# ETH_PHY_SFP.net
KiCad netlist of a schematic drawn in Altium Designer
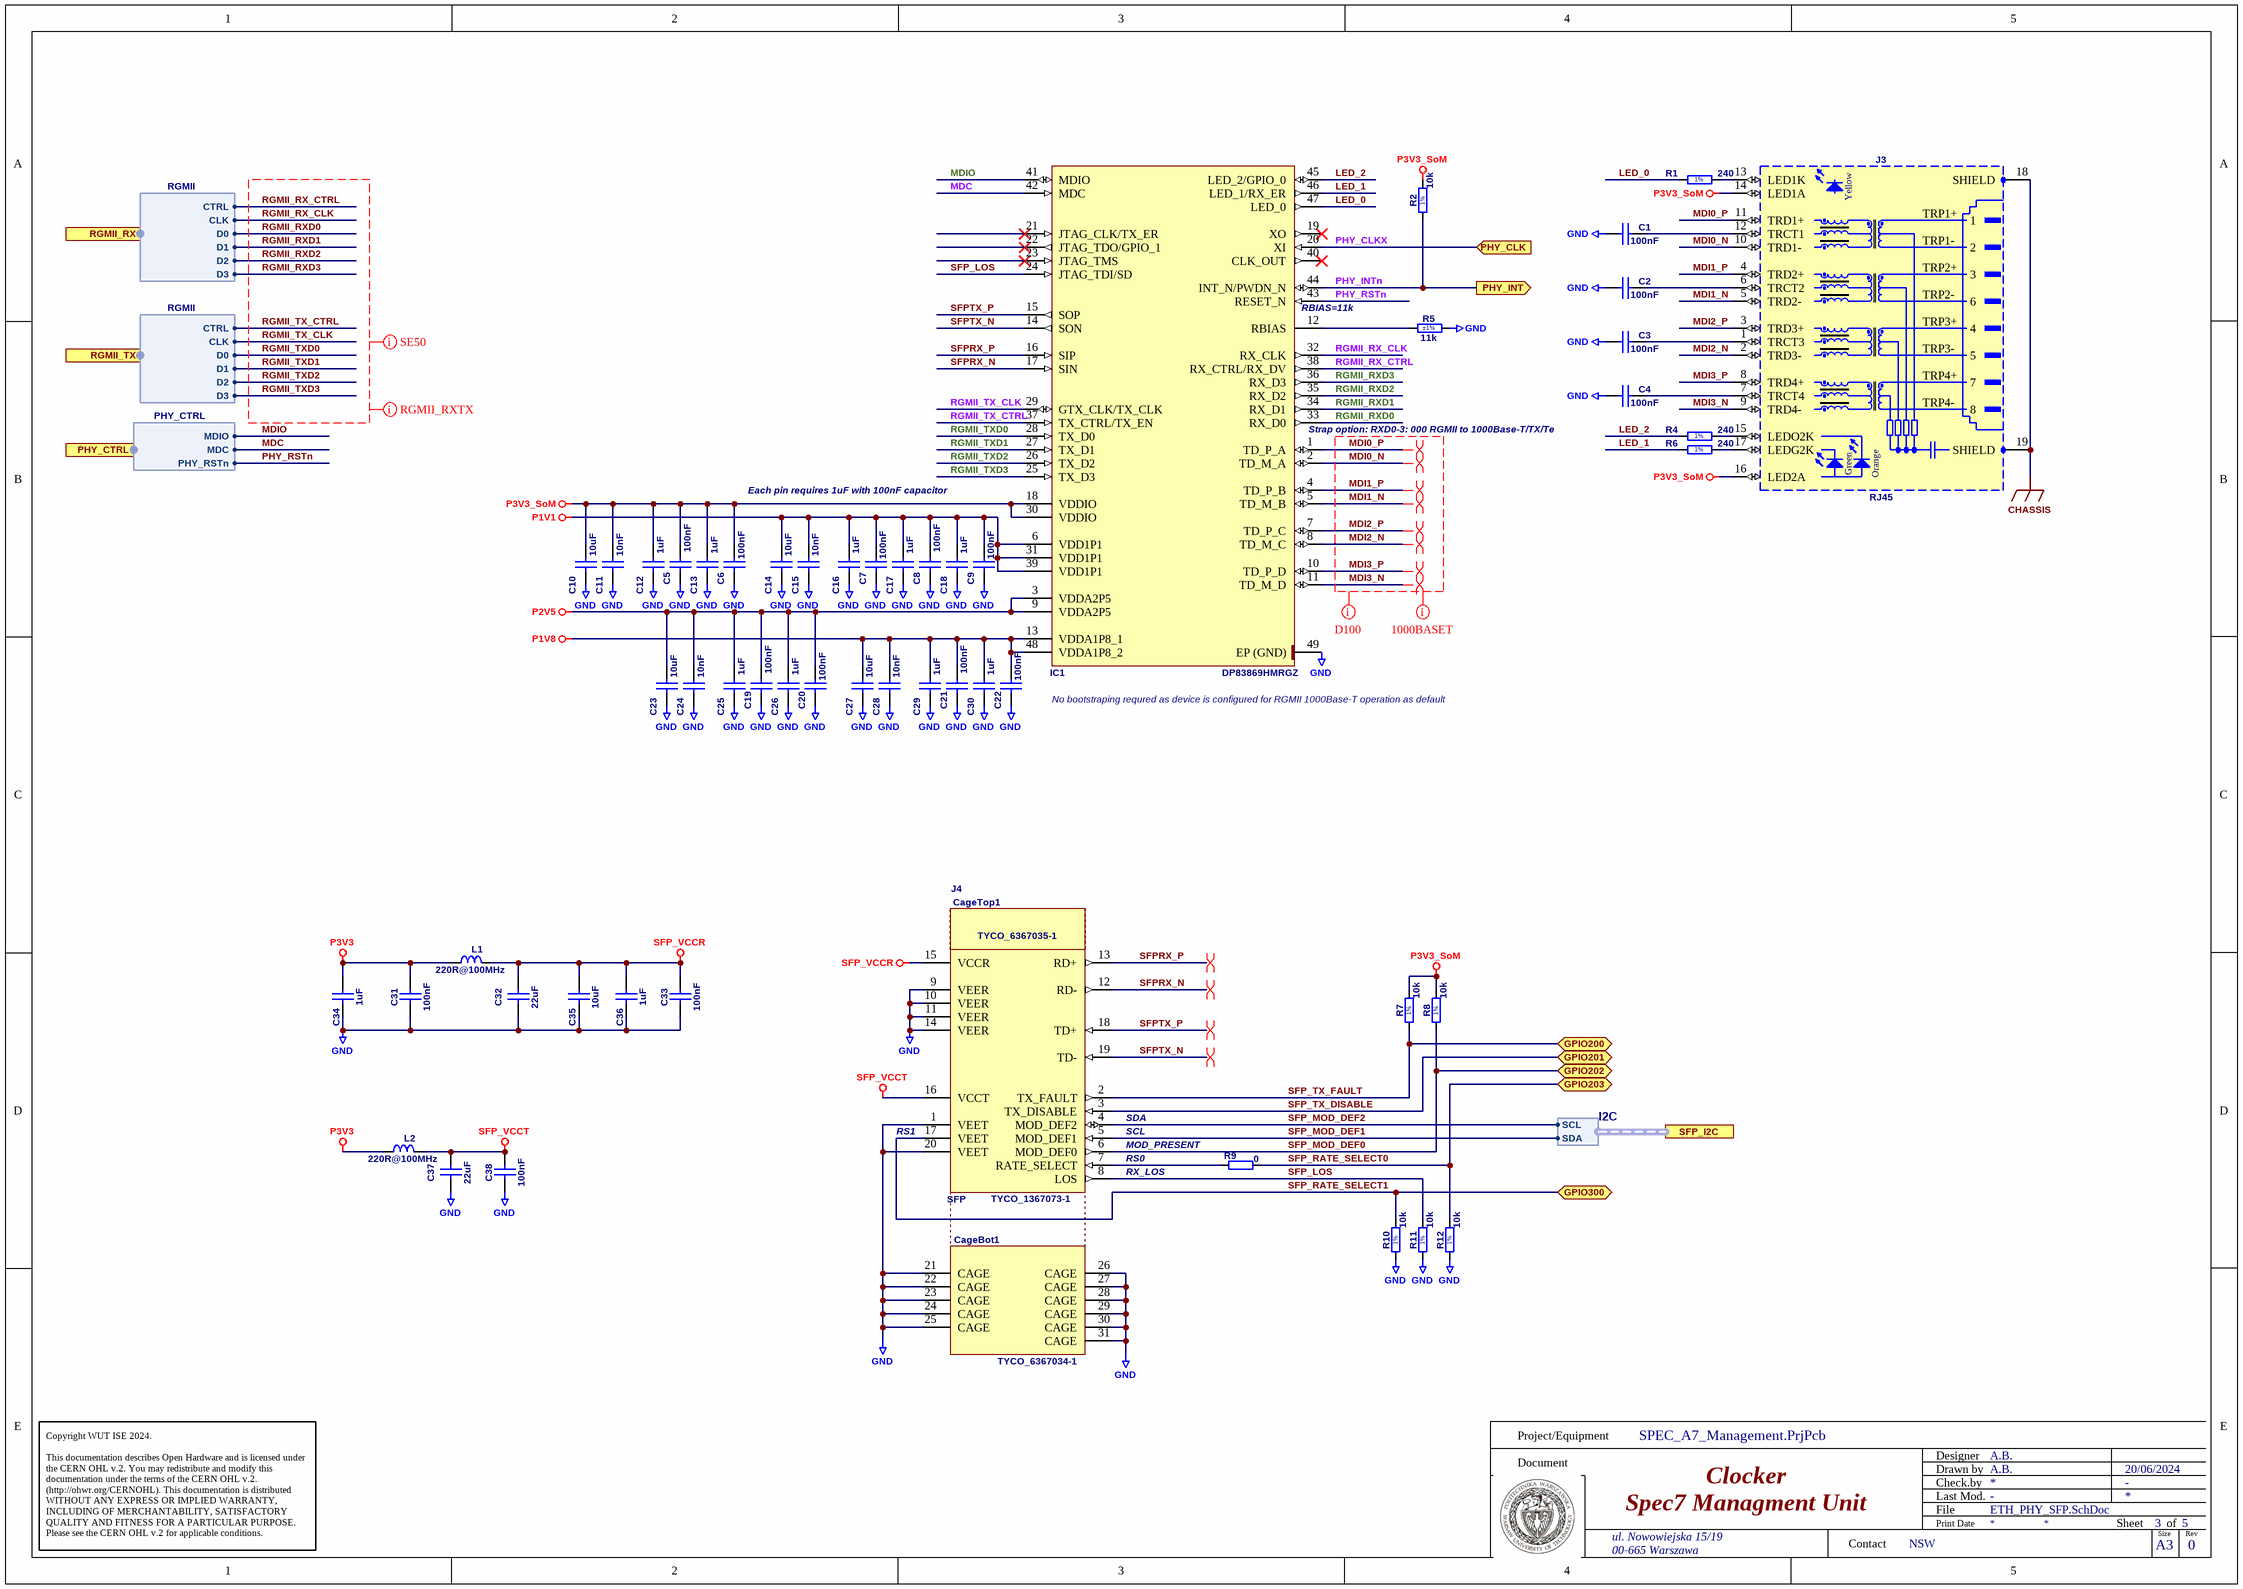
[diagram p0: ETH_PHY_SFP.SchDoc]

(export (version "E")
  (design (tool "Eeschema 10.0.6"))
  (components
    (comp (ref "C1")
      (value "100nF")
      (footprint "CAPC1005X55N")
      (description "Non-polarised capacitor")
      (fields
        (field (name "PART NUMBER") "CC0402_100NF_16V_10%_X7R")
        (field (name "VOLTAGE") "16V")
        (field (name "AUTHOR") "CERN DEM JLC")
      )
      (libsource (lib "Capacitors") (part "Capacitor - non polarized"))
    )
    (comp (ref "C2")
      (value "100nF")
      (footprint "CAPC1005X55N")
      (description "Non-polarised capacitor")
      (fields
        (field (name "PART NUMBER") "CC0402_100NF_16V_10%_X7R")
        (field (name "VOLTAGE") "16V")
        (field (name "AUTHOR") "CERN DEM JLC")
      )
      (libsource (lib "Capacitors") (part "Capacitor - non polarized"))
    )
    (comp (ref "C3")
      (value "100nF")
      (footprint "CAPC1005X55N")
      (description "Non-polarised capacitor")
      (fields
        (field (name "PART NUMBER") "CC0402_100NF_16V_10%_X7R")
        (field (name "VOLTAGE") "16V")
        (field (name "AUTHOR") "CERN DEM JLC")
      )
      (libsource (lib "Capacitors") (part "Capacitor - non polarized"))
    )
    (comp (ref "C4")
      (value "100nF")
      (footprint "CAPC1005X55N")
      (description "Non-polarised capacitor")
      (fields
        (field (name "PART NUMBER") "CC0402_100NF_16V_10%_X7R")
        (field (name "VOLTAGE") "16V")
        (field (name "AUTHOR") "CERN DEM JLC")
      )
      (libsource (lib "Capacitors") (part "Capacitor - non polarized"))
    )
    (comp (ref "C5")
      (value "100nF")
      (footprint "CAPC1005X55N")
      (description "Non-polarised capacitor")
      (fields
        (field (name "PART NUMBER") "CC0402_100NF_16V_10%_X7R")
        (field (name "VOLTAGE") "16V")
        (field (name "AUTHOR") "CERN DEM JLC")
      )
      (libsource (lib "Capacitors") (part "Capacitor - non polarized"))
    )
    (comp (ref "C6")
      (value "100nF")
      (footprint "CAPC1005X55N")
      (description "Non-polarised capacitor")
      (fields
        (field (name "PART NUMBER") "CC0402_100NF_16V_10%_X7R")
        (field (name "VOLTAGE") "16V")
        (field (name "AUTHOR") "CERN DEM JLC")
      )
      (libsource (lib "Capacitors") (part "Capacitor - non polarized"))
    )
    (comp (ref "C7")
      (value "100nF")
      (footprint "CAPC1005X55N")
      (description "Non-polarised capacitor")
      (fields
        (field (name "PART NUMBER") "CC0402_100NF_16V_10%_X7R")
        (field (name "VOLTAGE") "16V")
        (field (name "AUTHOR") "CERN DEM JLC")
      )
      (libsource (lib "Capacitors") (part "Capacitor - non polarized"))
    )
    (comp (ref "C8")
      (value "100nF")
      (footprint "CAPC1005X55N")
      (description "Non-polarised capacitor")
      (fields
        (field (name "PART NUMBER") "CC0402_100NF_16V_10%_X7R")
        (field (name "VOLTAGE") "16V")
        (field (name "AUTHOR") "CERN DEM JLC")
      )
      (libsource (lib "Capacitors") (part "Capacitor - non polarized"))
    )
    (comp (ref "C9")
      (value "100nF")
      (footprint "CAPC1005X55N")
      (description "Non-polarised capacitor")
      (fields
        (field (name "PART NUMBER") "CC0402_100NF_16V_10%_X7R")
        (field (name "VOLTAGE") "16V")
        (field (name "AUTHOR") "CERN DEM JLC")
      )
      (libsource (lib "Capacitors") (part "Capacitor - non polarized"))
    )
    (comp (ref "C10")
      (value "10uF")
      (footprint "CAPC1608X80N")
      (description "Non-polarised capacitor")
      (fields
        (field (name "PART NUMBER") "CC0603_10UF_16V_20%_X5R")
        (field (name "VOLTAGE") "16V")
        (field (name "AUTHOR") "CERN DEM MR")
      )
      (libsource (lib "Capacitors") (part "Capacitor - non polarized"))
    )
    (comp (ref "C11")
      (value "10nF")
      (footprint "CAPC1005X55N")
      (description "Non-polarised capacitor")
      (fields
        (field (name "PART NUMBER") "CC0402_10NF_16V_10%_X7R")
        (field (name "VOLTAGE") "16V")
        (field (name "AUTHOR") "CERN DEM JLC")
      )
      (libsource (lib "Capacitors") (part "Capacitor - non polarized"))
    )
    (comp (ref "C12")
      (value "1uF")
      (footprint "CAPC1005X55N")
      (description "Non-polarised capacitor")
      (fields
        (field (name "PART NUMBER") "CC0402_1UF_16V_10%_X5R")
        (field (name "VOLTAGE") "16V")
        (field (name "AUTHOR") "CERN DEM JLC")
      )
      (libsource (lib "Capacitors") (part "Capacitor - non polarized"))
    )
    (comp (ref "C13")
      (value "1uF")
      (footprint "CAPC1005X55N")
      (description "Non-polarised capacitor")
      (fields
        (field (name "PART NUMBER") "CC0402_1UF_16V_10%_X5R")
        (field (name "VOLTAGE") "16V")
        (field (name "AUTHOR") "CERN DEM JLC")
      )
      (libsource (lib "Capacitors") (part "Capacitor - non polarized"))
    )
    (comp (ref "C14")
      (value "10uF")
      (footprint "CAPC1608X80N")
      (description "Non-polarised capacitor")
      (fields
        (field (name "PART NUMBER") "CC0603_10UF_16V_20%_X5R")
        (field (name "VOLTAGE") "16V")
        (field (name "AUTHOR") "CERN DEM MR")
      )
      (libsource (lib "Capacitors") (part "Capacitor - non polarized"))
    )
    (comp (ref "C15")
      (value "10nF")
      (footprint "CAPC1005X55N")
      (description "Non-polarised capacitor")
      (fields
        (field (name "PART NUMBER") "CC0402_10NF_16V_10%_X7R")
        (field (name "VOLTAGE") "16V")
        (field (name "AUTHOR") "CERN DEM JLC")
      )
      (libsource (lib "Capacitors") (part "Capacitor - non polarized"))
    )
    (comp (ref "C16")
      (value "1uF")
      (footprint "CAPC1005X55N")
      (description "Non-polarised capacitor")
      (fields
        (field (name "PART NUMBER") "CC0402_1UF_16V_10%_X5R")
        (field (name "VOLTAGE") "16V")
        (field (name "AUTHOR") "CERN DEM JLC")
      )
      (libsource (lib "Capacitors") (part "Capacitor - non polarized"))
    )
    (comp (ref "C17")
      (value "1uF")
      (footprint "CAPC1005X55N")
      (description "Non-polarised capacitor")
      (fields
        (field (name "PART NUMBER") "CC0402_1UF_16V_10%_X5R")
        (field (name "VOLTAGE") "16V")
        (field (name "AUTHOR") "CERN DEM JLC")
      )
      (libsource (lib "Capacitors") (part "Capacitor - non polarized"))
    )
    (comp (ref "C18")
      (value "1uF")
      (footprint "CAPC1005X55N")
      (description "Non-polarised capacitor")
      (fields
        (field (name "PART NUMBER") "CC0402_1UF_16V_10%_X5R")
        (field (name "VOLTAGE") "16V")
        (field (name "AUTHOR") "CERN DEM JLC")
      )
      (libsource (lib "Capacitors") (part "Capacitor - non polarized"))
    )
    (comp (ref "C19")
      (value "100nF")
      (footprint "CAPC1005X55N")
      (description "Non-polarised capacitor")
      (fields
        (field (name "PART NUMBER") "CC0402_100NF_16V_10%_X7R")
        (field (name "VOLTAGE") "16V")
        (field (name "AUTHOR") "CERN DEM JLC")
      )
      (libsource (lib "Capacitors") (part "Capacitor - non polarized"))
    )
    (comp (ref "C20")
      (value "100nF")
      (footprint "CAPC1005X55N")
      (description "Non-polarised capacitor")
      (fields
        (field (name "PART NUMBER") "CC0402_100NF_16V_10%_X7R")
        (field (name "VOLTAGE") "16V")
        (field (name "AUTHOR") "CERN DEM JLC")
      )
      (libsource (lib "Capacitors") (part "Capacitor - non polarized"))
    )
    (comp (ref "C21")
      (value "100nF")
      (footprint "CAPC1005X55N")
      (description "Non-polarised capacitor")
      (fields
        (field (name "PART NUMBER") "CC0402_100NF_16V_10%_X7R")
        (field (name "VOLTAGE") "16V")
        (field (name "AUTHOR") "CERN DEM JLC")
      )
      (libsource (lib "Capacitors") (part "Capacitor - non polarized"))
    )
    (comp (ref "C22")
      (value "100nF")
      (footprint "CAPC1005X55N")
      (description "Non-polarised capacitor")
      (fields
        (field (name "PART NUMBER") "CC0402_100NF_16V_10%_X7R")
        (field (name "VOLTAGE") "16V")
        (field (name "AUTHOR") "CERN DEM JLC")
      )
      (libsource (lib "Capacitors") (part "Capacitor - non polarized"))
    )
    (comp (ref "C23")
      (value "10uF")
      (footprint "CAPC1608X80N")
      (description "Non-polarised capacitor")
      (fields
        (field (name "PART NUMBER") "CC0603_10UF_16V_20%_X5R")
        (field (name "VOLTAGE") "16V")
        (field (name "AUTHOR") "CERN DEM MR")
      )
      (libsource (lib "Capacitors") (part "Capacitor - non polarized"))
    )
    (comp (ref "C24")
      (value "10nF")
      (footprint "CAPC1005X55N")
      (description "Non-polarised capacitor")
      (fields
        (field (name "PART NUMBER") "CC0402_10NF_16V_10%_X7R")
        (field (name "VOLTAGE") "16V")
        (field (name "AUTHOR") "CERN DEM JLC")
      )
      (libsource (lib "Capacitors") (part "Capacitor - non polarized"))
    )
    (comp (ref "C25")
      (value "1uF")
      (footprint "CAPC1005X55N")
      (description "Non-polarised capacitor")
      (fields
        (field (name "PART NUMBER") "CC0402_1UF_16V_10%_X5R")
        (field (name "VOLTAGE") "16V")
        (field (name "AUTHOR") "CERN DEM JLC")
      )
      (libsource (lib "Capacitors") (part "Capacitor - non polarized"))
    )
    (comp (ref "C26")
      (value "1uF")
      (footprint "CAPC1005X55N")
      (description "Non-polarised capacitor")
      (fields
        (field (name "PART NUMBER") "CC0402_1UF_16V_10%_X5R")
        (field (name "VOLTAGE") "16V")
        (field (name "AUTHOR") "CERN DEM JLC")
      )
      (libsource (lib "Capacitors") (part "Capacitor - non polarized"))
    )
    (comp (ref "C27")
      (value "10uF")
      (footprint "CAPC1608X80N")
      (description "Non-polarised capacitor")
      (fields
        (field (name "PART NUMBER") "CC0603_10UF_16V_20%_X5R")
        (field (name "VOLTAGE") "16V")
        (field (name "AUTHOR") "CERN DEM MR")
      )
      (libsource (lib "Capacitors") (part "Capacitor - non polarized"))
    )
    (comp (ref "C28")
      (value "10nF")
      (footprint "CAPC1005X55N")
      (description "Non-polarised capacitor")
      (fields
        (field (name "PART NUMBER") "CC0402_10NF_16V_10%_X7R")
        (field (name "VOLTAGE") "16V")
        (field (name "AUTHOR") "CERN DEM JLC")
      )
      (libsource (lib "Capacitors") (part "Capacitor - non polarized"))
    )
    (comp (ref "C29")
      (value "1uF")
      (footprint "CAPC1005X55N")
      (description "Non-polarised capacitor")
      (fields
        (field (name "PART NUMBER") "CC0402_1UF_16V_10%_X5R")
        (field (name "VOLTAGE") "16V")
        (field (name "AUTHOR") "CERN DEM JLC")
      )
      (libsource (lib "Capacitors") (part "Capacitor - non polarized"))
    )
    (comp (ref "C30")
      (value "1uF")
      (footprint "CAPC1005X55N")
      (description "Non-polarised capacitor")
      (fields
        (field (name "PART NUMBER") "CC0402_1UF_16V_10%_X5R")
        (field (name "VOLTAGE") "16V")
        (field (name "AUTHOR") "CERN DEM JLC")
      )
      (libsource (lib "Capacitors") (part "Capacitor - non polarized"))
    )
    (comp (ref "C31")
      (value "100nF")
      (footprint "CAPC1005X55N")
      (description "Non-polarised capacitor")
      (fields
        (field (name "PART NUMBER") "CC0402_100NF_16V_10%_X7R")
        (field (name "VOLTAGE") "16V")
        (field (name "AUTHOR") "CERN DEM JLC")
      )
      (libsource (lib "Capacitors") (part "Capacitor - non polarized"))
    )
    (comp (ref "C32")
      (value "22uF")
      (footprint "CAPC2012X135N")
      (description "Non-polarised capacitor")
      (fields
        (field (name "MANUFACTURER PART NUMBER") "CC0805_22UF_16V_10%_X5R")
        (field (name "MANUFACTURER") "GENERIC")
        (field (name "AUTHOR") "CERN DEM JLC")
      )
      (libsource (lib "Capacitors") (part "Capacitor - non polarized"))
    )
    (comp (ref "C33")
      (value "100nF")
      (footprint "CAPC1005X55N")
      (description "Non-polarised capacitor")
      (fields
        (field (name "PART NUMBER") "CC0402_100NF_16V_10%_X7R")
        (field (name "VOLTAGE") "16V")
        (field (name "AUTHOR") "CERN DEM JLC")
      )
      (libsource (lib "Capacitors") (part "Capacitor - non polarized"))
    )
    (comp (ref "C34")
      (value "1uF")
      (footprint "CAPC1005X55N")
      (description "Non-polarised capacitor")
      (fields
        (field (name "PART NUMBER") "CC0402_1UF_16V_10%_X5R")
        (field (name "VOLTAGE") "16V")
        (field (name "AUTHOR") "CERN DEM JLC")
      )
      (libsource (lib "Capacitors") (part "Capacitor - non polarized"))
    )
    (comp (ref "C35")
      (value "10uF")
      (footprint "CAPC1608X80N")
      (description "Non-polarised capacitor")
      (fields
        (field (name "PART NUMBER") "CC0603_10UF_16V_20%_X5R")
        (field (name "VOLTAGE") "16V")
        (field (name "AUTHOR") "CERN DEM MR")
      )
      (libsource (lib "Capacitors") (part "Capacitor - non polarized"))
    )
    (comp (ref "C36")
      (value "1uF")
      (footprint "CAPC1005X55N")
      (description "Non-polarised capacitor")
      (fields
        (field (name "PART NUMBER") "CC0402_1UF_16V_10%_X5R")
        (field (name "VOLTAGE") "16V")
        (field (name "AUTHOR") "CERN DEM JLC")
      )
      (libsource (lib "Capacitors") (part "Capacitor - non polarized"))
    )
    (comp (ref "C37")
      (value "22uF")
      (footprint "CAPC2012X135N")
      (description "Non-polarised capacitor")
      (fields
        (field (name "MANUFACTURER PART NUMBER") "CC0805_22UF_16V_10%_X5R")
        (field (name "MANUFACTURER") "GENERIC")
        (field (name "AUTHOR") "CERN DEM JLC")
      )
      (libsource (lib "Capacitors") (part "Capacitor - non polarized"))
    )
    (comp (ref "C38")
      (value "100nF")
      (footprint "CAPC1005X55N")
      (description "Non-polarised capacitor")
      (fields
        (field (name "PART NUMBER") "CC0402_100NF_16V_10%_X7R")
        (field (name "VOLTAGE") "16V")
        (field (name "AUTHOR") "CERN DEM JLC")
      )
      (libsource (lib "Capacitors") (part "Capacitor - non polarized"))
    )
    (comp (ref "CageBot1")
      (value "SFP")
      (footprint "TYCO_6367034-1")
      (description "SFP  Cage Bottom (Small Form-factor Pluggable)")
      (fields
        (field (name "PART NUMBER") "TYCO_6367034-1")
        (field (name "MANUFACTURER") "TYCO ELECTRONICS")
        (field (name "MANUFACTURER PART NUMBER") "TYCO_6367034-1")
        (field (name "AUTHOR") "CERN DEM JLC")
      )
      (libsource (lib "Connectors") (part "SFPx1_Cage Bottom"))
    )
    (comp (ref "CageTop1")
      (value "SFP")
      (footprint "TYCO_6367035-1")
      (description "SFP  Cage Top (Small Form-factor Pluggable)")
      (fields
        (field (name "PART NUMBER") "TYCO_6367035-1")
        (field (name "MANUFACTURER") "TYCO ELECTRONICS")
        (field (name "MANUFACTURER PART NUMBER") "TYCO_6367035-1")
        (field (name "AUTHOR") "CERN DEM JLC")
      )
      (libsource (lib "Connectors") (part "SFPx1_Cage Top"))
    )
    (comp (ref "IC1")
      (value "DP83869HMRGZ")
      (footprint "QFN50P700X700X100-49N-S420")
      (fields (field (name "MANUFACTURER") "TEXAS INSTRUMENTS") (field (name "AUTHOR") "CERN DEM HF"))
      (libsource (lib "ICs And Semiconductors") (part "DP83869HMRGZ"))
    )
    (comp (ref "J3")
      (value "RJ45")
      (footprint "BEL_L829-1J1T-43")
      (description "1 Port, RJ45, Gigabit Ethernet, MagJack Connector Module With Yellow And Green/Orange LEDs")
      (fields
        (field (name "PART NUMBER") "BELFUSE_L829-1J1T-43")
        (field (name "MANUFACTURER") "BEL MAGNETIC SOLUTIONS")
        (field (name "AUTHOR") "CERN DEM JLC")
      )
      (libsource (lib "Miscellaneous") (part "BELFUSE_L829-1J1T-43"))
    )
    (comp (ref "J4")
      (value "SFP")
      (footprint "TYCO_1367073-1")
      (description "20 Position SFP  Connector (Small Form-factor Pluggable)")
      (fields
        (field (name "PART NUMBER") "TYCO_1367073-1")
        (field (name "MANUFACTURER") "TYCO ELECTRONICS")
        (field (name "MANUFACTURER PART NUMBER") "1367073-1")
        (field (name "AUTHOR") "CERN DEM JLC")
      )
      (libsource (lib "Connectors") (part "SFPx1"))
    )
    (comp (ref "L1")
      (value "220R@100MHz")
      (footprint "INDC2012X105N")
      (description "Inductor")
      (fields
        (field (name "PART NUMBER") "IND0805_MURATA_BLM21PG221SN1D")
        (field (name "POWER") "2A")
        (field (name "AUTHOR") "CERN DEM JLC")
      )
      (libsource (lib "Inductors & Transformers") (part "Inductor"))
    )
    (comp (ref "L2")
      (value "220R@100MHz")
      (footprint "INDC2012X105N")
      (description "Inductor")
      (fields
        (field (name "PART NUMBER") "IND0805_MURATA_BLM21PG221SN1D")
        (field (name "POWER") "2A")
        (field (name "AUTHOR") "CERN DEM JLC")
      )
      (libsource (lib "Inductors & Transformers") (part "Inductor"))
    )
    (comp (ref "R1")
      (value "240")
      (footprint "RESC1005X40N")
      (description "Resistor - 1%")
      (fields
        (field (name "PART NUMBER") "R0402_240R_1%_0.0625W_100PPM")
        (field (name "POWER") "0.0625W")
        (field (name "AUTHOR") "CERN DEM JLC")
      )
      (libsource (lib "Resistors") (part "Resistor - 1%"))
    )
    (comp (ref "R2")
      (value "10k")
      (footprint "RESC1005X40N")
      (description "Resistor - 1%")
      (fields
        (field (name "PART NUMBER") "R0402_10K_1%_0.0625W_100PPM")
        (field (name "POWER") "0.0625W")
        (field (name "AUTHOR") "CERN DEM JLC")
      )
      (libsource (lib "Resistors") (part "Resistor - 1%"))
    )
    (comp (ref "R4")
      (value "240")
      (footprint "RESC1005X40N")
      (description "Resistor - 1%")
      (fields
        (field (name "PART NUMBER") "R0402_240R_1%_0.0625W_100PPM")
        (field (name "POWER") "0.0625W")
        (field (name "AUTHOR") "CERN DEM JLC")
      )
      (libsource (lib "Resistors") (part "Resistor - 1%"))
    )
    (comp (ref "R5")
      (value "11k")
      (footprint "RESC1005X40N")
      (description "Resistor - 1%")
      (fields
        (field (name "TOLERANCE") "±1%")
        (field (name "PART NUMBER") "R0402_11K_1%_0.0625W_100PPM")
        (field (name "POWER") "0.0625W")
        (field (name "AUTHOR") "CERN DEM JLC")
      )
      (libsource (lib "Resistors") (part "Resistor - 1%"))
    )
    (comp (ref "R6")
      (value "240")
      (footprint "RESC1005X40N")
      (description "Resistor - 1%")
      (fields
        (field (name "PART NUMBER") "R0402_240R_1%_0.0625W_100PPM")
        (field (name "POWER") "0.0625W")
        (field (name "AUTHOR") "CERN DEM JLC")
      )
      (libsource (lib "Resistors") (part "Resistor - 1%"))
    )
    (comp (ref "R7")
      (value "10k")
      (footprint "RESC1005X40N")
      (description "Resistor - 1%")
      (fields
        (field (name "PART NUMBER") "R0402_10K_1%_0.0625W_100PPM")
        (field (name "POWER") "0.0625W")
        (field (name "AUTHOR") "CERN DEM JLC")
      )
      (libsource (lib "Resistors") (part "Resistor - 1%"))
    )
    (comp (ref "R8")
      (value "10k")
      (footprint "RESC1005X40N")
      (description "Resistor - 1%")
      (fields
        (field (name "PART NUMBER") "R0402_10K_1%_0.0625W_100PPM")
        (field (name "POWER") "0.0625W")
        (field (name "AUTHOR") "CERN DEM JLC")
      )
      (libsource (lib "Resistors") (part "Resistor - 1%"))
    )
    (comp (ref "R9")
      (value "0")
      (footprint "RESC1005X40N")
      (description "Resistor")
      (fields
        (field (name "PART NUMBER") "R0402_0R_JUMPER")
        (field (name "MANUFACTURER") "GENERIC")
        (field (name "AUTHOR") "CERN DEM JLC")
      )
      (libsource (lib "Resistors") (part "Resistor"))
    )
    (comp (ref "R10")
      (value "10k")
      (footprint "RESC1005X40N")
      (description "Resistor - 1%")
      (fields
        (field (name "PART NUMBER") "R0402_10K_1%_0.0625W_100PPM")
        (field (name "POWER") "0.0625W")
        (field (name "AUTHOR") "CERN DEM JLC")
      )
      (libsource (lib "Resistors") (part "Resistor - 1%"))
    )
    (comp (ref "R11")
      (value "10k")
      (footprint "RESC1005X40N")
      (description "Resistor - 1%")
      (fields
        (field (name "PART NUMBER") "R0402_10K_1%_0.0625W_100PPM")
        (field (name "POWER") "0.0625W")
        (field (name "AUTHOR") "CERN DEM JLC")
      )
      (libsource (lib "Resistors") (part "Resistor - 1%"))
    )
    (comp (ref "R12")
      (value "10k")
      (footprint "RESC1005X40N")
      (description "Resistor - 1%")
      (fields
        (field (name "PART NUMBER") "R0402_10K_1%_0.0625W_100PPM")
        (field (name "POWER") "0.0625W")
        (field (name "AUTHOR") "CERN DEM JLC")
      )
      (libsource (lib "Resistors") (part "Resistor - 1%"))
    )
  )
  (nets
    (net (code "4") (name "/LED_0") (class "Default")
      (node (ref "IC1") (pin "47") (pinfunction "LED_0_47") (pintype "output"))
      (node (ref "R1") (pin "1") (pinfunction "1_1") (pintype "passive"))
    )
    (net (code "5") (name "/LED_1") (class "Default")
      (node (ref "IC1") (pin "46") (pinfunction "LED_1/RX_ER_46") (pintype "output"))
      (node (ref "R6") (pin "1") (pinfunction "1_1") (pintype "passive"))
    )
    (net (code "6") (name "/LED_2") (class "Default")
      (node (ref "IC1") (pin "45") (pinfunction "LED_2/GPIO_0_45") (pintype "bidirectional"))
      (node (ref "R4") (pin "1") (pinfunction "1_1") (pintype "passive"))
    )
    (net (code "7") (name "/MDC") (class "Default")
      (node (ref "IC1") (pin "42") (pinfunction "MDC_42") (pintype "input"))
    )
    (net (code "8") (name "/MDI0_N") (class "Default")
      (node (ref "IC1") (pin "2") (pinfunction "TD_M_A_2") (pintype "bidirectional"))
      (node (ref "J3") (pin "10") (pinfunction "TRD1-_10") (pintype "bidirectional"))
    )
    (net (code "9") (name "/MDI0_P") (class "Default")
      (node (ref "IC1") (pin "1") (pinfunction "TD_P_A_1") (pintype "bidirectional"))
      (node (ref "J3") (pin "11") (pinfunction "TRD1+_11") (pintype "bidirectional"))
    )
    (net (code "10") (name "/MDI1_N") (class "Default")
      (node (ref "IC1") (pin "5") (pinfunction "TD_M_B_5") (pintype "bidirectional"))
      (node (ref "J3") (pin "5") (pinfunction "TRD2-_5") (pintype "bidirectional"))
    )
    (net (code "11") (name "/MDI1_P") (class "Default")
      (node (ref "IC1") (pin "4") (pinfunction "TD_P_B_4") (pintype "bidirectional"))
      (node (ref "J3") (pin "4") (pinfunction "TRD2+_4") (pintype "bidirectional"))
    )
    (net (code "12") (name "/MDI2_N") (class "Default")
      (node (ref "IC1") (pin "8") (pinfunction "TD_M_C_8") (pintype "bidirectional"))
      (node (ref "J3") (pin "2") (pinfunction "TRD3-_2") (pintype "bidirectional"))
    )
    (net (code "13") (name "/MDI2_P") (class "Default")
      (node (ref "IC1") (pin "7") (pinfunction "TD_P_C_7") (pintype "bidirectional"))
      (node (ref "J3") (pin "3") (pinfunction "TRD3+_3") (pintype "bidirectional"))
    )
    (net (code "14") (name "/MDI3_N") (class "Default")
      (node (ref "IC1") (pin "11") (pinfunction "TD_M_D_11") (pintype "bidirectional"))
      (node (ref "J3") (pin "9") (pinfunction "TRD4-_9") (pintype "bidirectional"))
    )
    (net (code "15") (name "/MDI3_P") (class "Default")
      (node (ref "IC1") (pin "10") (pinfunction "TD_P_D_10") (pintype "bidirectional"))
      (node (ref "J3") (pin "8") (pinfunction "TRD4+_8") (pintype "bidirectional"))
    )
    (net (code "16") (name "/MDIO") (class "Default")
      (node (ref "IC1") (pin "41") (pinfunction "MDIO_41") (pintype "bidirectional"))
    )
    (net (code "17") (name "/PHY_CLKX") (class "Default")
      (node (ref "IC1") (pin "20") (pinfunction "XI_20") (pintype "input"))
    )
    (net (code "18") (name "/PHY_INTn") (class "Default")
      (node (ref "IC1") (pin "44") (pinfunction "INT_N/PWDN_N_44") (pintype "bidirectional"))
      (node (ref "R2") (pin "1") (pinfunction "1_1") (pintype "passive"))
    )
    (net (code "19") (name "/PHY_RSTn") (class "Default")
      (node (ref "IC1") (pin "43") (pinfunction "RESET_N_43") (pintype "input"))
    )
    (net (code "20") (name "/RGMII_RXD0") (class "Default")
      (node (ref "IC1") (pin "33") (pinfunction "RX_D0_33") (pintype "output"))
    )
    (net (code "21") (name "/RGMII_RXD1") (class "Default")
      (node (ref "IC1") (pin "34") (pinfunction "RX_D1_34") (pintype "output"))
    )
    (net (code "22") (name "/RGMII_RXD2") (class "Default")
      (node (ref "IC1") (pin "35") (pinfunction "RX_D2_35") (pintype "output"))
    )
    (net (code "23") (name "/RGMII_RXD3") (class "Default")
      (node (ref "IC1") (pin "36") (pinfunction "RX_D3_36") (pintype "output"))
    )
    (net (code "24") (name "/RGMII_RX_CLK") (class "Default")
      (node (ref "IC1") (pin "32") (pinfunction "RX_CLK_32") (pintype "output"))
    )
    (net (code "25") (name "/RGMII_RX_CTRL") (class "Default")
      (node (ref "IC1") (pin "38") (pinfunction "RX_CTRL/RX_DV_38") (pintype "output"))
    )
    (net (code "26") (name "/RGMII_TXD0") (class "Default")
      (node (ref "IC1") (pin "28") (pinfunction "TX_D0_28") (pintype "input"))
    )
    (net (code "27") (name "/RGMII_TXD1") (class "Default")
      (node (ref "IC1") (pin "27") (pinfunction "TX_D1_27") (pintype "input"))
    )
    (net (code "28") (name "/RGMII_TXD2") (class "Default")
      (node (ref "IC1") (pin "26") (pinfunction "TX_D2_26") (pintype "input"))
    )
    (net (code "29") (name "/RGMII_TXD3") (class "Default")
      (node (ref "IC1") (pin "25") (pinfunction "TX_D3_25") (pintype "input"))
    )
    (net (code "30") (name "/RGMII_TX_CLK") (class "Default")
      (node (ref "IC1") (pin "29") (pinfunction "GTX_CLK/TX_CLK_29") (pintype "bidirectional"))
    )
    (net (code "31") (name "/RGMII_TX_CTRL") (class "Default")
      (node (ref "IC1") (pin "37") (pinfunction "TX_CTRL/TX_EN_37") (pintype "input"))
    )
    (net (code "32") (name "/SFPRX_N") (class "Default")
      (node (ref "IC1") (pin "17") (pinfunction "SIN_17") (pintype "input"))
      (node (ref "J4") (pin "12") (pinfunction "RD-_12") (pintype "output"))
    )
    (net (code "33") (name "/SFPRX_P") (class "Default")
      (node (ref "IC1") (pin "16") (pinfunction "SIP_16") (pintype "input"))
      (node (ref "J4") (pin "13") (pinfunction "RD+_13") (pintype "output"))
    )
    (net (code "34") (name "/SFPTX_N") (class "Default")
      (node (ref "IC1") (pin "14") (pinfunction "SON_14") (pintype "output"))
      (node (ref "J4") (pin "19") (pinfunction "TD-_19") (pintype "input"))
    )
    (net (code "35") (name "/SFPTX_P") (class "Default")
      (node (ref "IC1") (pin "15") (pinfunction "SOP_15") (pintype "output"))
      (node (ref "J4") (pin "18") (pinfunction "TD+_18") (pintype "input"))
    )
    (net (code "36") (name "/SFP_LOS") (class "Default")
      (node (ref "IC1") (pin "24") (pinfunction "JTAG_TDI/SD_24") (pintype "input"))
      (node (ref "J4") (pin "8") (pinfunction "LOS_8") (pintype "output"))
      (node (ref "R11") (pin "2") (pinfunction "2_2") (pintype "passive"))
    )
    (net (code "37") (name "/SFP_MOD_DEF0") (class "Default")
      (node (ref "J4") (pin "6") (pinfunction "MOD_DEF0_6") (pintype "output"))
      (node (ref "R8") (pin "1") (pinfunction "1_1") (pintype "passive"))
    )
    (net (code "38") (name "/SFP_MOD_DEF1") (class "Default")
      (node (ref "J4") (pin "5") (pinfunction "MOD_DEF1_5") (pintype "input"))
    )
    (net (code "39") (name "/SFP_MOD_DEF2") (class "Default")
      (node (ref "J4") (pin "4") (pinfunction "MOD_DEF2_4") (pintype "bidirectional"))
    )
    (net (code "40") (name "/SFP_RATE_SELECT0") (class "Default")
      (node (ref "R12") (pin "2") (pinfunction "2_2") (pintype "passive"))
      (node (ref "R9") (pin "2") (pinfunction "2_2") (pintype "passive"))
    )
    (net (code "41") (name "/SFP_RATE_SELECT1") (class "Default")
      (node (ref "J4") (pin "17") (pinfunction "VEET_17") (pintype "power_in"))
      (node (ref "R10") (pin "2") (pinfunction "2_2") (pintype "passive"))
    )
    (net (code "42") (name "/SFP_TX_DISABLE") (class "Default")
      (node (ref "J4") (pin "3") (pinfunction "TX_DISABLE_3") (pintype "input"))
    )
    (net (code "43") (name "/SFP_TX_FAULT") (class "Default")
      (node (ref "J4") (pin "2") (pinfunction "TX_FAULT_2") (pintype "output"))
      (node (ref "R7") (pin "1") (pinfunction "1_1") (pintype "passive"))
    )
    (net (code "47") (name "CHASSIS") (class "Default")
      (node (ref "J3") (pin "18") (pinfunction "SHIELD_18") (pintype "power_in"))
      (node (ref "J3") (pin "19") (pinfunction "SHIELD_19") (pintype "power_in"))
    )
    (net (code "48") (name "GND") (class "Default")
      (node (ref "C1") (pin "1") (pinfunction "1_1") (pintype "passive"))
      (node (ref "C10") (pin "1") (pinfunction "1_1") (pintype "passive"))
      (node (ref "C11") (pin "1") (pinfunction "1_1") (pintype "passive"))
      (node (ref "C12") (pin "1") (pinfunction "1_1") (pintype "passive"))
      (node (ref "C13") (pin "1") (pinfunction "1_1") (pintype "passive"))
      (node (ref "C14") (pin "1") (pinfunction "1_1") (pintype "passive"))
      (node (ref "C15") (pin "1") (pinfunction "1_1") (pintype "passive"))
      (node (ref "C16") (pin "1") (pinfunction "1_1") (pintype "passive"))
      (node (ref "C17") (pin "1") (pinfunction "1_1") (pintype "passive"))
      (node (ref "C18") (pin "1") (pinfunction "1_1") (pintype "passive"))
      (node (ref "C19") (pin "1") (pinfunction "1_1") (pintype "passive"))
      (node (ref "C2") (pin "1") (pinfunction "1_1") (pintype "passive"))
      (node (ref "C20") (pin "1") (pinfunction "1_1") (pintype "passive"))
      (node (ref "C21") (pin "1") (pinfunction "1_1") (pintype "passive"))
      (node (ref "C22") (pin "1") (pinfunction "1_1") (pintype "passive"))
      (node (ref "C23") (pin "1") (pinfunction "1_1") (pintype "passive"))
      (node (ref "C24") (pin "1") (pinfunction "1_1") (pintype "passive"))
      (node (ref "C25") (pin "1") (pinfunction "1_1") (pintype "passive"))
      (node (ref "C26") (pin "1") (pinfunction "1_1") (pintype "passive"))
      (node (ref "C27") (pin "1") (pinfunction "1_1") (pintype "passive"))
      (node (ref "C28") (pin "1") (pinfunction "1_1") (pintype "passive"))
      (node (ref "C29") (pin "1") (pinfunction "1_1") (pintype "passive"))
      (node (ref "C3") (pin "1") (pinfunction "1_1") (pintype "passive"))
      (node (ref "C30") (pin "1") (pinfunction "1_1") (pintype "passive"))
      (node (ref "C31") (pin "1") (pinfunction "1_1") (pintype "passive"))
      (node (ref "C32") (pin "1") (pinfunction "1_1") (pintype "passive"))
      (node (ref "C33") (pin "1") (pinfunction "1_1") (pintype "passive"))
      (node (ref "C34") (pin "1") (pinfunction "1_1") (pintype "passive"))
      (node (ref "C35") (pin "1") (pinfunction "1_1") (pintype "passive"))
      (node (ref "C36") (pin "1") (pinfunction "1_1") (pintype "passive"))
      (node (ref "C37") (pin "1") (pinfunction "1_1") (pintype "passive"))
      (node (ref "C38") (pin "1") (pinfunction "1_1") (pintype "passive"))
      (node (ref "C4") (pin "1") (pinfunction "1_1") (pintype "passive"))
      (node (ref "C5") (pin "1") (pinfunction "1_1") (pintype "passive"))
      (node (ref "C6") (pin "1") (pinfunction "1_1") (pintype "passive"))
      (node (ref "C7") (pin "1") (pinfunction "1_1") (pintype "passive"))
      (node (ref "C8") (pin "1") (pinfunction "1_1") (pintype "passive"))
      (node (ref "C9") (pin "1") (pinfunction "1_1") (pintype "passive"))
      (node (ref "CageBot1") (pin "21") (pinfunction "CAGE_21") (pintype "power_in"))
      (node (ref "CageBot1") (pin "22") (pinfunction "CAGE_22") (pintype "power_in"))
      (node (ref "CageBot1") (pin "23") (pinfunction "CAGE_23") (pintype "power_in"))
      (node (ref "CageBot1") (pin "24") (pinfunction "CAGE_24") (pintype "power_in"))
      (node (ref "CageBot1") (pin "25") (pinfunction "CAGE_25") (pintype "power_in"))
      (node (ref "CageBot1") (pin "26") (pinfunction "CAGE_26") (pintype "power_in"))
      (node (ref "CageBot1") (pin "27") (pinfunction "CAGE_27") (pintype "power_in"))
      (node (ref "CageBot1") (pin "28") (pinfunction "CAGE_28") (pintype "power_in"))
      (node (ref "CageBot1") (pin "29") (pinfunction "CAGE_29") (pintype "power_in"))
      (node (ref "CageBot1") (pin "30") (pinfunction "CAGE_30") (pintype "power_in"))
      (node (ref "CageBot1") (pin "31") (pinfunction "CAGE_31") (pintype "power_in"))
      (node (ref "IC1") (pin "49") (pinfunction "EP_(GND)_49") (pintype "power_in"))
      (node (ref "J4") (pin "1") (pinfunction "VEET_1") (pintype "power_in"))
      (node (ref "J4") (pin "10") (pinfunction "VEER_10") (pintype "power_in"))
      (node (ref "J4") (pin "11") (pinfunction "VEER_11") (pintype "power_in"))
      (node (ref "J4") (pin "14") (pinfunction "VEER_14") (pintype "power_in"))
      (node (ref "J4") (pin "20") (pinfunction "VEET_20") (pintype "power_in"))
      (node (ref "J4") (pin "9") (pinfunction "VEER_9") (pintype "power_in"))
      (node (ref "R10") (pin "1") (pinfunction "1_1") (pintype "passive"))
      (node (ref "R11") (pin "1") (pinfunction "1_1") (pintype "passive"))
      (node (ref "R12") (pin "1") (pinfunction "1_1") (pintype "passive"))
      (node (ref "R5") (pin "2") (pinfunction "2_2") (pintype "passive"))
    )
    (net (code "49") (name "Net-(IC1-RBIAS)") (class "Default")
      (node (ref "IC1") (pin "12") (pinfunction "RBIAS_12") (pintype "passive"))
      (node (ref "R5") (pin "1") (pinfunction "1_1") (pintype "passive"))
    )
    (net (code "50") (name "Net-(J3-LED1K)") (class "Default")
      (node (ref "J3") (pin "13") (pinfunction "LED1K_13") (pintype "bidirectional"))
      (node (ref "R1") (pin "2") (pinfunction "2_2") (pintype "passive"))
    )
    (net (code "51") (name "Net-(J3-LEDG2K)") (class "Default")
      (node (ref "J3") (pin "17") (pinfunction "LEDG2K_17") (pintype "bidirectional"))
      (node (ref "R6") (pin "2") (pinfunction "2_2") (pintype "passive"))
    )
    (net (code "52") (name "Net-(J3-LEDO2K)") (class "Default")
      (node (ref "J3") (pin "15") (pinfunction "LEDO2K_15") (pintype "bidirectional"))
      (node (ref "R4") (pin "2") (pinfunction "2_2") (pintype "passive"))
    )
    (net (code "53") (name "Net-(J3-TRCT1)") (class "Default")
      (node (ref "C1") (pin "2") (pinfunction "2_2") (pintype "passive"))
      (node (ref "J3") (pin "12") (pinfunction "TRCT1_12") (pintype "bidirectional"))
    )
    (net (code "54") (name "Net-(J3-TRCT2)") (class "Default")
      (node (ref "C2") (pin "2") (pinfunction "2_2") (pintype "passive"))
      (node (ref "J3") (pin "6") (pinfunction "TRCT2_6") (pintype "bidirectional"))
    )
    (net (code "55") (name "Net-(J3-TRCT3)") (class "Default")
      (node (ref "C3") (pin "2") (pinfunction "2_2") (pintype "passive"))
      (node (ref "J3") (pin "1") (pinfunction "TRCT3_1") (pintype "bidirectional"))
    )
    (net (code "56") (name "Net-(J3-TRCT4)") (class "Default")
      (node (ref "C4") (pin "2") (pinfunction "2_2") (pintype "passive"))
      (node (ref "J3") (pin "7") (pinfunction "TRCT4_7") (pintype "bidirectional"))
    )
    (net (code "57") (name "Net-(J4-RATE_SELECT)") (class "Default")
      (node (ref "J4") (pin "7") (pinfunction "RATE_SELECT_7") (pintype "input"))
      (node (ref "R9") (pin "1") (pinfunction "1_1") (pintype "passive"))
    )
    (net (code "58") (name "P1V1") (class "Default")
      (node (ref "C14") (pin "2") (pinfunction "2_2") (pintype "passive"))
      (node (ref "C15") (pin "2") (pinfunction "2_2") (pintype "passive"))
      (node (ref "C16") (pin "2") (pinfunction "2_2") (pintype "passive"))
      (node (ref "C17") (pin "2") (pinfunction "2_2") (pintype "passive"))
      (node (ref "C18") (pin "2") (pinfunction "2_2") (pintype "passive"))
      (node (ref "C7") (pin "2") (pinfunction "2_2") (pintype "passive"))
      (node (ref "C8") (pin "2") (pinfunction "2_2") (pintype "passive"))
      (node (ref "C9") (pin "2") (pinfunction "2_2") (pintype "passive"))
      (node (ref "IC1") (pin "31") (pinfunction "VDD1P1_31") (pintype "power_in"))
      (node (ref "IC1") (pin "39") (pinfunction "VDD1P1_39") (pintype "power_in"))
      (node (ref "IC1") (pin "6") (pinfunction "VDD1P1_6") (pintype "power_in"))
    )
    (net (code "59") (name "P1V8") (class "Default")
      (node (ref "C21") (pin "2") (pinfunction "2_2") (pintype "passive"))
      (node (ref "C22") (pin "2") (pinfunction "2_2") (pintype "passive"))
      (node (ref "C27") (pin "2") (pinfunction "2_2") (pintype "passive"))
      (node (ref "C28") (pin "2") (pinfunction "2_2") (pintype "passive"))
      (node (ref "C29") (pin "2") (pinfunction "2_2") (pintype "passive"))
      (node (ref "C30") (pin "2") (pinfunction "2_2") (pintype "passive"))
      (node (ref "IC1") (pin "13") (pinfunction "VDDA1P8_1_13") (pintype "power_in"))
      (node (ref "IC1") (pin "48") (pinfunction "VDDA1P8_2_48") (pintype "power_in"))
    )
    (net (code "60") (name "P2V5") (class "Default")
      (node (ref "C19") (pin "2") (pinfunction "2_2") (pintype "passive"))
      (node (ref "C20") (pin "2") (pinfunction "2_2") (pintype "passive"))
      (node (ref "C23") (pin "2") (pinfunction "2_2") (pintype "passive"))
      (node (ref "C24") (pin "2") (pinfunction "2_2") (pintype "passive"))
      (node (ref "C25") (pin "2") (pinfunction "2_2") (pintype "passive"))
      (node (ref "C26") (pin "2") (pinfunction "2_2") (pintype "passive"))
      (node (ref "IC1") (pin "3") (pinfunction "VDDA2P5_3") (pintype "power_in"))
      (node (ref "IC1") (pin "9") (pinfunction "VDDA2P5_9") (pintype "power_in"))
    )
    (net (code "61") (name "P3V3") (class "Default")
      (node (ref "C31") (pin "2") (pinfunction "2_2") (pintype "passive"))
      (node (ref "C34") (pin "2") (pinfunction "2_2") (pintype "passive"))
      (node (ref "L1") (pin "1") (pinfunction "1_1") (pintype "passive"))
      (node (ref "L2") (pin "1") (pinfunction "1_1") (pintype "passive"))
    )
    (net (code "62") (name "P3V3_SoM") (class "Default")
      (node (ref "C10") (pin "2") (pinfunction "2_2") (pintype "passive"))
      (node (ref "C11") (pin "2") (pinfunction "2_2") (pintype "passive"))
      (node (ref "C12") (pin "2") (pinfunction "2_2") (pintype "passive"))
      (node (ref "C13") (pin "2") (pinfunction "2_2") (pintype "passive"))
      (node (ref "C5") (pin "2") (pinfunction "2_2") (pintype "passive"))
      (node (ref "C6") (pin "2") (pinfunction "2_2") (pintype "passive"))
      (node (ref "IC1") (pin "18") (pinfunction "VDDIO_18") (pintype "power_in"))
      (node (ref "IC1") (pin "30") (pinfunction "VDDIO_30") (pintype "power_in"))
      (node (ref "J3") (pin "14") (pinfunction "LED1A_14") (pintype "bidirectional"))
      (node (ref "J3") (pin "16") (pinfunction "LED2A_16") (pintype "bidirectional"))
      (node (ref "R2") (pin "2") (pinfunction "2_2") (pintype "passive"))
      (node (ref "R7") (pin "2") (pinfunction "2_2") (pintype "passive"))
      (node (ref "R8") (pin "2") (pinfunction "2_2") (pintype "passive"))
    )
    (net (code "63") (name "SFP_VCCR") (class "Default")
      (node (ref "C32") (pin "2") (pinfunction "2_2") (pintype "passive"))
      (node (ref "C33") (pin "2") (pinfunction "2_2") (pintype "passive"))
      (node (ref "C35") (pin "2") (pinfunction "2_2") (pintype "passive"))
      (node (ref "C36") (pin "2") (pinfunction "2_2") (pintype "passive"))
      (node (ref "J4") (pin "15") (pinfunction "VCCR_15") (pintype "power_in"))
      (node (ref "L1") (pin "2") (pinfunction "2_2") (pintype "passive"))
    )
    (net (code "64") (name "SFP_VCCT") (class "Default")
      (node (ref "C37") (pin "2") (pinfunction "2_2") (pintype "passive"))
      (node (ref "C38") (pin "2") (pinfunction "2_2") (pintype "passive"))
      (node (ref "J4") (pin "16") (pinfunction "VCCT_16") (pintype "power_in"))
      (node (ref "L2") (pin "2") (pinfunction "2_2") (pintype "passive"))
    )
    (net (code "65") (name "unconnected-(IC1-CLK_OUT-Pad40)") (class "Default")
      (node (ref "IC1") (pin "40") (pinfunction "CLK_OUT_40") (pintype "output+no_connect"))
    )
    (net (code "66") (name "unconnected-(IC1-JTAG_CLK{slash}TX_ER-Pad21)") (class "Default")
      (node (ref "IC1") (pin "21") (pinfunction "JTAG_CLK/TX_ER_21") (pintype "input+no_connect"))
    )
    (net (code "67") (name "unconnected-(IC1-JTAG_TDO{slash}GPIO_1-Pad22)") (class "Default")
      (node (ref "IC1") (pin "22") (pinfunction "JTAG_TDO/GPIO_1_22") (pintype "output+no_connect"))
    )
    (net (code "68") (name "unconnected-(IC1-JTAG_TMS-Pad23)") (class "Default")
      (node (ref "IC1") (pin "23") (pinfunction "JTAG_TMS_23") (pintype "input+no_connect"))
    )
    (net (code "69") (name "unconnected-(IC1-XO-Pad19)") (class "Default")
      (node (ref "IC1") (pin "19") (pinfunction "XO_19") (pintype "output+no_connect"))
    )
  )
)
